# fpga-rx2.net
KiCad netlist of a schematic drawn in Altium Designer
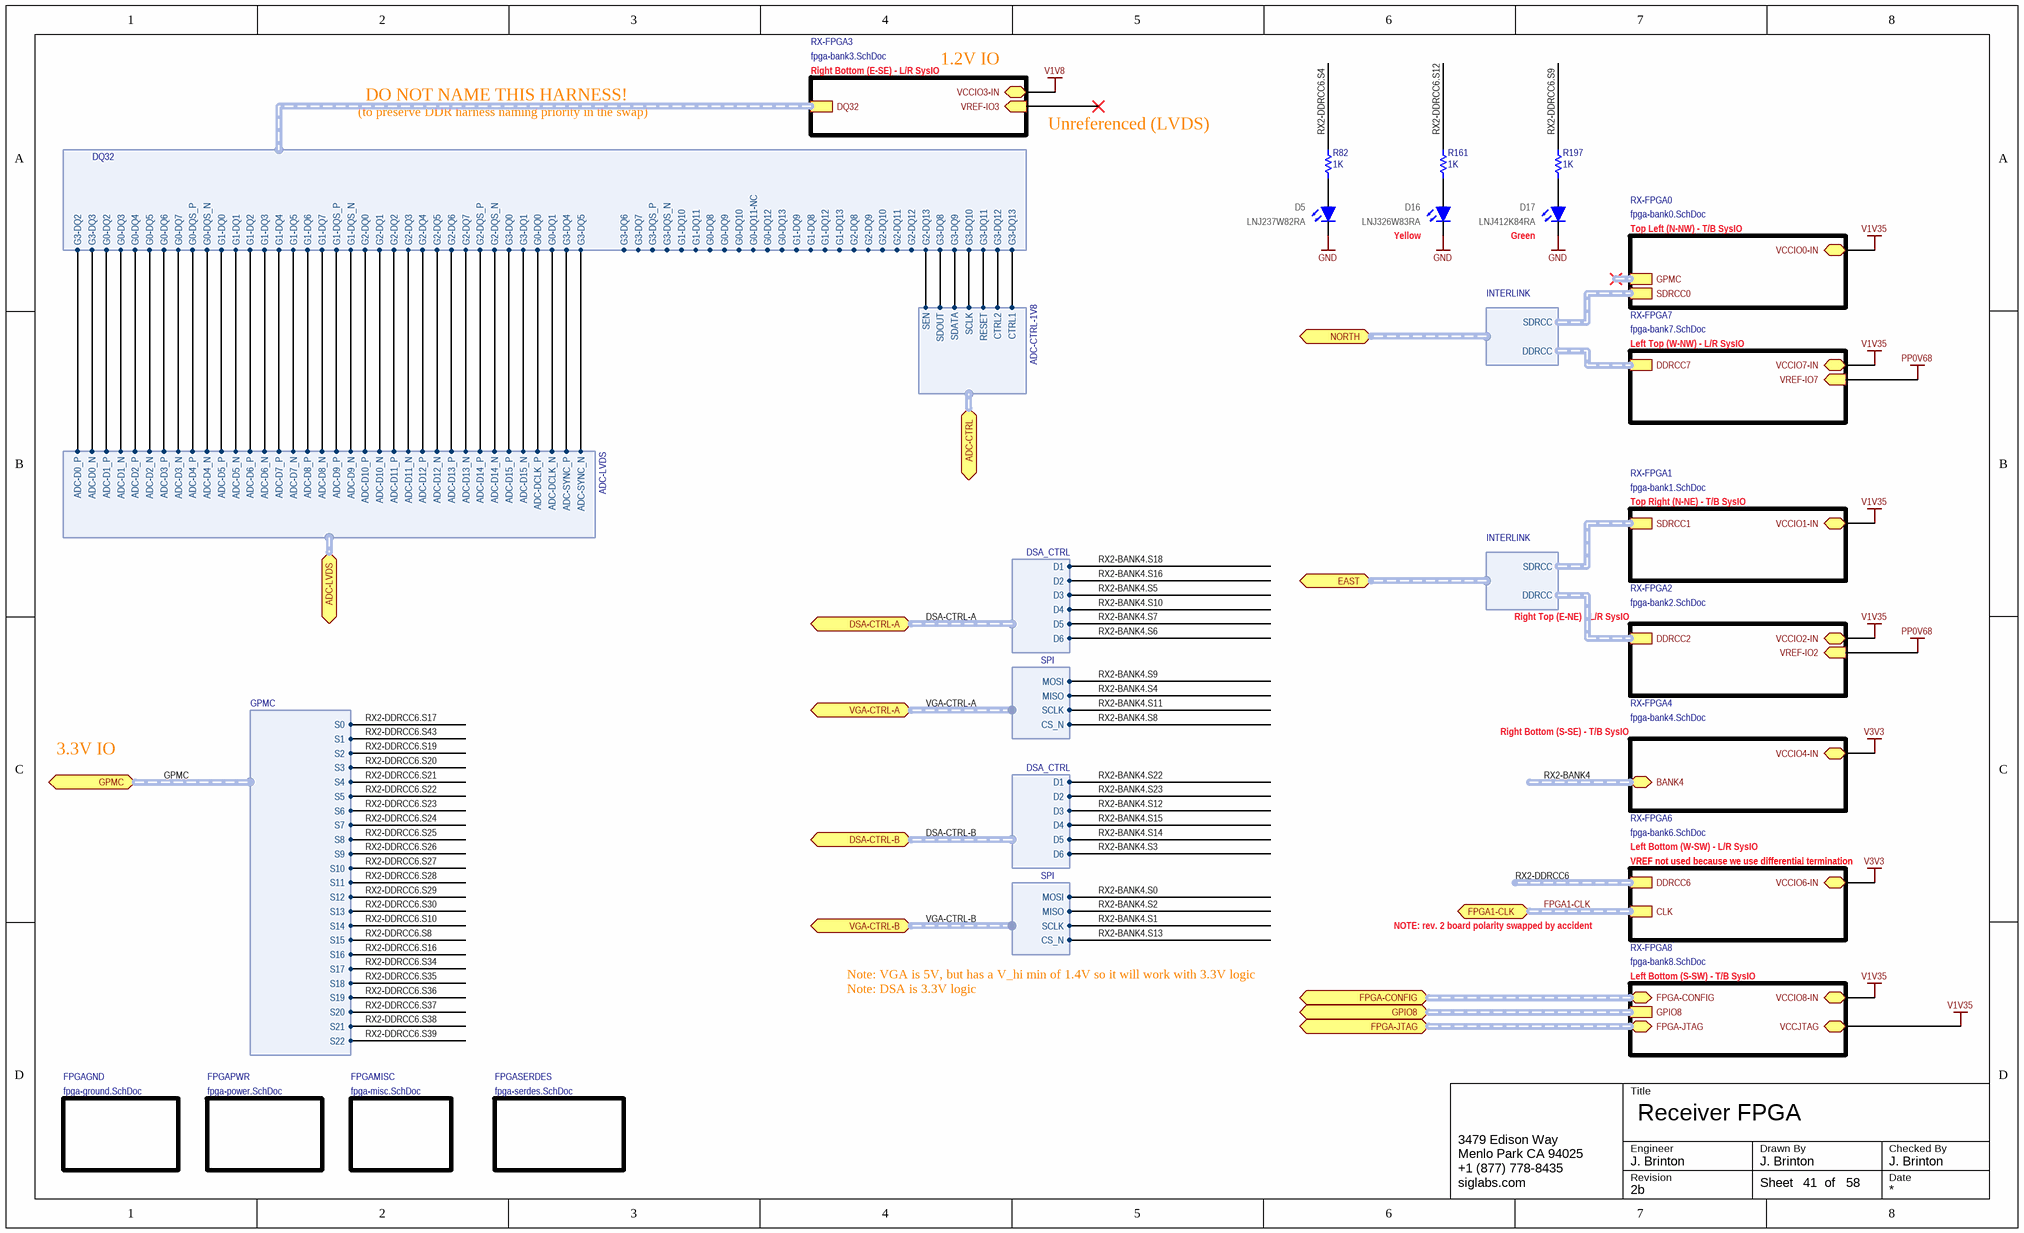
[diagram p0: fpga-rx2.SchDoc]

(export (version "E")
  (design (tool "Eeschema 10.0.6"))
  (components
    (comp (ref "D5")
      (value "LNJ237W82RA")
      (footprint "0603_LED")
      (description "LED, SMT 0603, Color Red, 5mA, 1.85V")
      (fields (field (name "MANUFACTURER") "Panasonic"))
      (libsource (lib "generic") (part "LED0603RD"))
    )
    (comp (ref "D16")
      (value "LNJ326W83RA")
      (footprint "0603_LED")
      (description "LED, SMT 0603, Color Green, 10mA, 2.05V")
      (fields (field (name "MANUFACTURER") "Panasonic"))
      (libsource (lib "generic") (part "LED0603GR"))
    )
    (comp (ref "D17")
      (value "LNJ412K84RA")
      (footprint "0603_LED")
      (description "LED, SMT 0603, Color Yellow, 10mA, 2.05V")
      (fields (field (name "MANUFACTURER") "Panasonic"))
      (libsource (lib "generic") (part "LED0603Y"))
    )
    (comp (ref "R82")
      (value "1K")
      (footprint "generic:0402")
      (description "Thick Film Resistor 1k ±1% 0402")
      (fields (field (name "MANUFACTURER") "Yageo") (field (name "TOLERANCE") "±1%"))
      (libsource (lib "Graviton") (part "RES 0402"))
    )
    (comp (ref "R161")
      (value "1K")
      (footprint "generic:0402")
      (description "Thick Film Resistor 1k ±1% 0402")
      (fields (field (name "MANUFACTURER") "Yageo") (field (name "TOLERANCE") "±1%"))
      (libsource (lib "Graviton") (part "RES 0402"))
    )
    (comp (ref "R197")
      (value "1K")
      (footprint "generic:0402")
      (description "Thick Film Resistor 1k ±1% 0402")
      (fields (field (name "MANUFACTURER") "Yageo") (field (name "TOLERANCE") "±1%"))
      (libsource (lib "Graviton") (part "RES 0402"))
    )
  )
  (nets
    (net (code "47") (name "/RX2-DDRCC6.S4") (class "Default")
      (node (ref "R82") (pin "2") (pinfunction "2_2") (pintype "passive"))
    )
    (net (code "49") (name "/RX2-DDRCC6.S9") (class "Default")
      (node (ref "R197") (pin "2") (pinfunction "2_2") (pintype "passive"))
    )
    (net (code "51") (name "/RX2-DDRCC6.S12") (class "Default")
      (node (ref "R161") (pin "2") (pinfunction "2_2") (pintype "passive"))
    )
    (net (code "85") (name "GND") (class "Default")
      (node (ref "D16") (pin "2") (pinfunction "K_2") (pintype "passive"))
      (node (ref "D17") (pin "2") (pinfunction "K_2") (pintype "passive"))
      (node (ref "D5") (pin "2") (pinfunction "K_2") (pintype "passive"))
    )
    (net (code "86") (name "Net-(D5-A)") (class "Default")
      (node (ref "D5") (pin "1") (pinfunction "A_1") (pintype "passive"))
      (node (ref "R82") (pin "1") (pinfunction "1_1") (pintype "passive"))
    )
    (net (code "87") (name "Net-(D16-A)") (class "Default")
      (node (ref "D16") (pin "1") (pinfunction "A_1") (pintype "passive"))
      (node (ref "R161") (pin "1") (pinfunction "1_1") (pintype "passive"))
    )
    (net (code "88") (name "Net-(D17-A)") (class "Default")
      (node (ref "D17") (pin "1") (pinfunction "A_1") (pintype "passive"))
      (node (ref "R197") (pin "1") (pinfunction "1_1") (pintype "passive"))
    )
  )
)
